# LED_Driver.net
KiCad netlist of a schematic drawn in Altium Designer
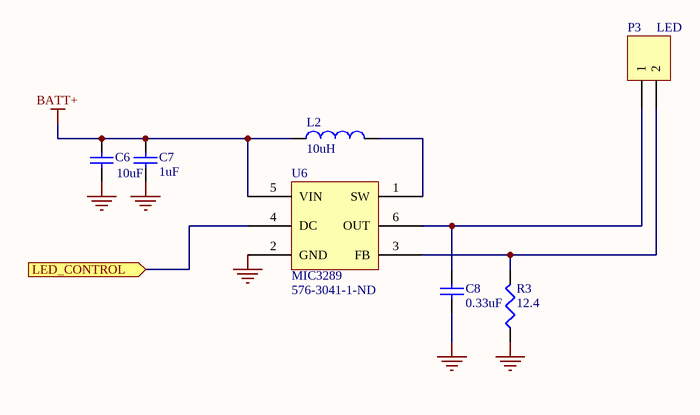
[diagram p0: LED Driver.SchDoc]

(export (version "E")
  (design (tool "Eeschema 10.0.6"))
  (components
    (comp (ref "C6")
      (value "10uF")
      (footprint "CAPC3216L")
      (description "Capacitor")
      (fields (field (name "Comment") "Cap") (field (name "PUBLISHER") "Altium Limited"))
      (libsource (lib "Miscellaneous Devices") (part "Cap"))
    )
    (comp (ref "C7")
      (value "1uF")
      (footprint "CAPC3216L")
      (description "Capacitor (Semiconductor SIM Model)")
      (fields (field (name "Comment") "Cap Semi") (field (name "PUBLISHER") "Altium Limited"))
      (libsource (lib "Miscellaneous Devices") (part "Cap Semi"))
    )
    (comp (ref "C8")
      (value "0.33uF")
      (footprint "CAPC3216L")
      (description "Capacitor (Semiconductor SIM Model)")
      (fields (field (name "Comment") "Cap Semi") (field (name "PUBLISHER") "Altium Limited"))
      (libsource (lib "Miscellaneous Devices") (part "Cap Semi"))
    )
    (comp (ref "L2")
      (value "10uH")
      (footprint "MURATA SMT INDUCTOR")
      (description "Inductor")
      (fields (field (name "PUBLISHER") "Altium Limited"))
      (libsource (lib "Miscellaneous Devices") (part "Inductor"))
    )
    (comp (ref "P3")
      (value "LED")
      (footprint "2MM JST PH - 2 PIN")
      (description "Header, 2-Pin")
      (fields (field (name "PUBLISHER") "Altium Limited"))
      (libsource (lib "Miscellaneous Connectors") (part "Header 2"))
    )
    (comp (ref "R3")
      (value "12.4")
      (footprint "RESC3216L")
      (description "Resistor")
      (fields (field (name "Comment") "Res3") (field (name "PUBLISHER") "Altium Limited"))
      (libsource (lib "Miscellaneous Devices") (part "Res3"))
    )
    (comp (ref "U6")
      (value "MIC3289")
      (footprint "SOT-23_A")
      (fields (field (name "SUPPLIER PART NUMBER 1") "576-3041-1-ND"))
      (libsource (lib "Altium Footprints") (part "MIC3289"))
    )
  )
  (nets
    (net (code "1") (name "/LED_CONTROL") (class "Default")
      (node (ref "U6") (pin "4") (pinfunction "DC_4") (pintype "passive"))
    )
    (net (code "2") (name "BATT+") (class "Default")
      (node (ref "C6") (pin "2") (pinfunction "2_2") (pintype "passive"))
      (node (ref "C7") (pin "2") (pinfunction "2_2") (pintype "passive"))
      (node (ref "L2") (pin "1") (pinfunction "1_1") (pintype "passive"))
      (node (ref "U6") (pin "5") (pinfunction "VIN_5") (pintype "passive"))
    )
    (net (code "3") (name "GND") (class "Default")
      (node (ref "C6") (pin "1") (pinfunction "1_1") (pintype "passive"))
      (node (ref "C7") (pin "1") (pinfunction "1_1") (pintype "passive"))
      (node (ref "C8") (pin "1") (pinfunction "1_1") (pintype "passive"))
      (node (ref "R3") (pin "1") (pinfunction "1_1") (pintype "passive"))
      (node (ref "U6") (pin "2") (pinfunction "GND_2") (pintype "passive"))
    )
    (net (code "4") (name "Net-(U6-FB)") (class "Default")
      (node (ref "P3") (pin "2") (pinfunction "2_2") (pintype "passive"))
      (node (ref "R3") (pin "2") (pinfunction "2_2") (pintype "passive"))
      (node (ref "U6") (pin "3") (pinfunction "FB_3") (pintype "passive"))
    )
    (net (code "5") (name "Net-(U6-OUT)") (class "Default")
      (node (ref "C8") (pin "2") (pinfunction "2_2") (pintype "passive"))
      (node (ref "P3") (pin "1") (pinfunction "1_1") (pintype "passive"))
      (node (ref "U6") (pin "6") (pinfunction "OUT_6") (pintype "passive"))
    )
    (net (code "6") (name "Net-(U6-SW)") (class "Default")
      (node (ref "L2") (pin "2") (pinfunction "2_2") (pintype "passive"))
      (node (ref "U6") (pin "1") (pinfunction "SW_1") (pintype "passive"))
    )
  )
)
